# CM_FPGA_B0-1.net
KiCad netlist of a schematic drawn in Altium Designer
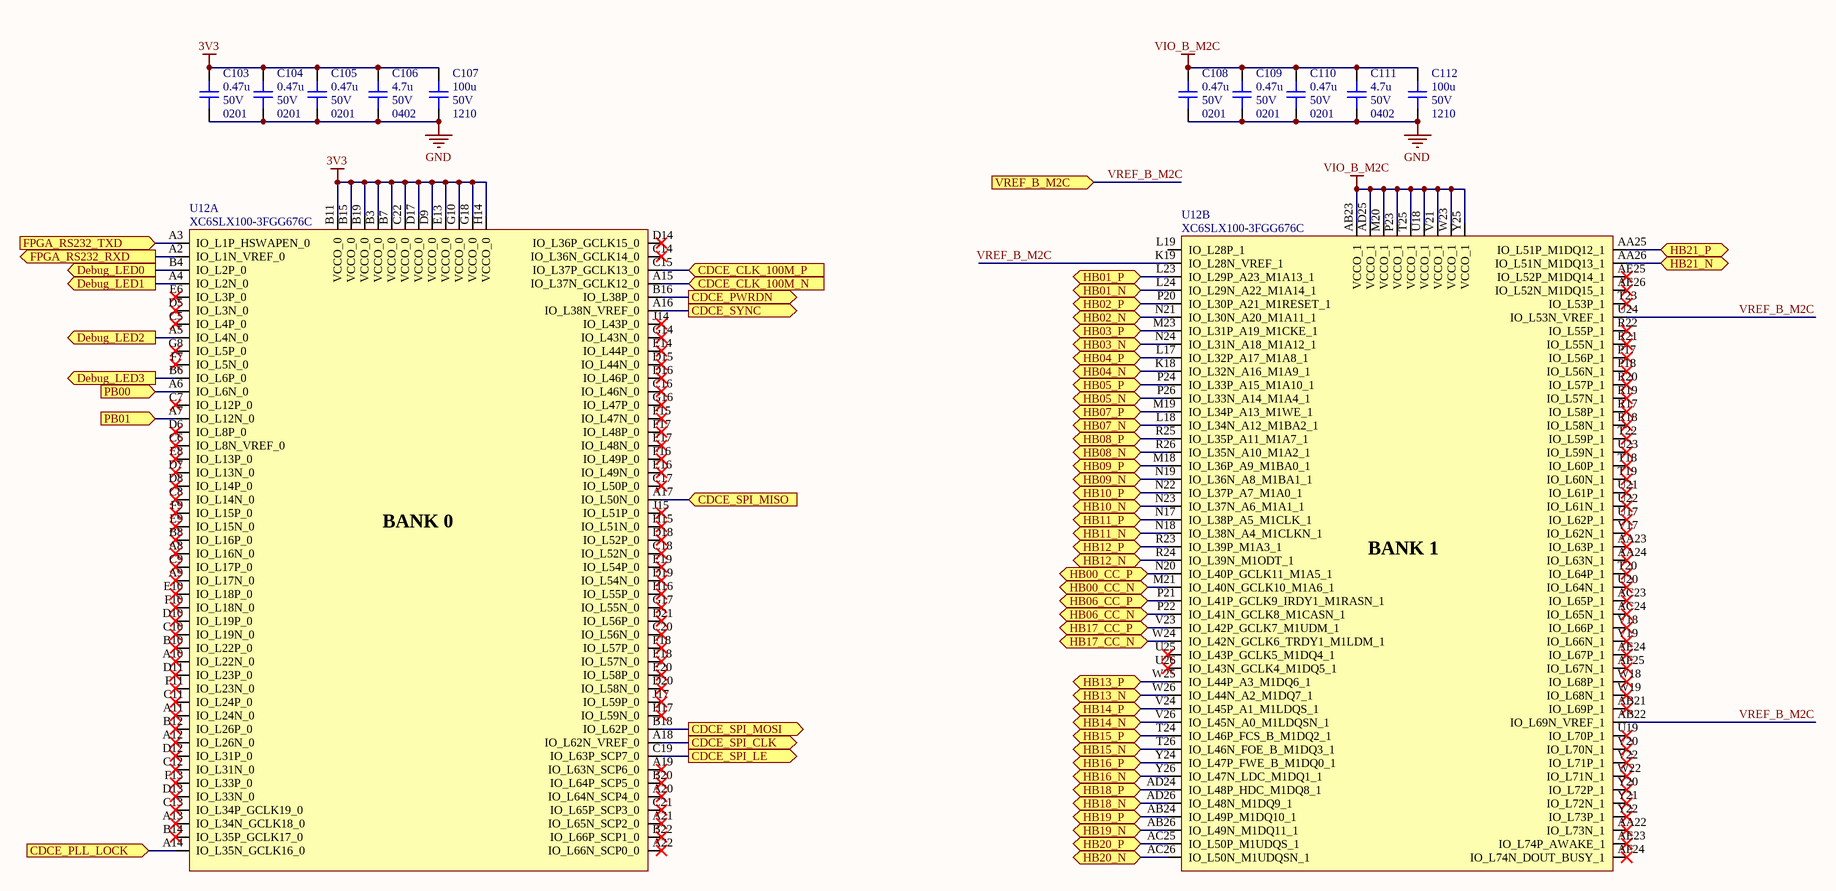
[diagram p0: CM_FPGA_B0-1.SchDoc]

(export (version "E")
  (design (tool "Eeschema 10.0.6"))
  (components
    (comp (ref "C103")
      (value "0.47u")
      (footprint "CAP_0201")
      (description "CAP - 0201")
      (fields
        (field (name "VOLTAGE") "50V")
        (field (name "PACKAGE") "0201")
        (field (name "CREATEDBY") "Jonathan Bouchard")
      )
      (libsource (lib "S7CAS_Lib2019_REV1_00") (part "CAP - 0201"))
    )
    (comp (ref "C104")
      (value "0.47u")
      (footprint "CAP_0201")
      (description "CAP - 0201")
      (fields
        (field (name "VOLTAGE") "50V")
        (field (name "PACKAGE") "0201")
        (field (name "CREATEDBY") "Jonathan Bouchard")
      )
      (libsource (lib "S7CAS_Lib2019_REV1_00") (part "CAP - 0201"))
    )
    (comp (ref "C105")
      (value "0.47u")
      (footprint "CAP_0201")
      (description "CAP - 0201")
      (fields
        (field (name "VOLTAGE") "50V")
        (field (name "PACKAGE") "0201")
        (field (name "CREATEDBY") "Jonathan Bouchard")
      )
      (libsource (lib "S7CAS_Lib2019_REV1_00") (part "CAP - 0201"))
    )
    (comp (ref "C106")
      (value "4.7u")
      (footprint "CAP_0402")
      (description "CAP - 0402")
      (fields
        (field (name "VOLTAGE") "50V")
        (field (name "PACKAGE") "0402")
        (field (name "CREATEDBY") "Jonathan Bouchard")
      )
      (libsource (lib "S7CAS_Lib2019_REV1_00") (part "CAP - 0402"))
    )
    (comp (ref "C107")
      (value "100u")
      (footprint "CAP_1210")
      (description "CAP - 1210")
      (fields
        (field (name "VOLTAGE") "50V")
        (field (name "PACKAGE") "1210")
        (field (name "CREATEDBY") "Jonathan Bouchard")
      )
      (libsource (lib "S7CAS_Lib2019_REV1_00") (part "CAP - 1210"))
    )
    (comp (ref "C108")
      (value "0.47u")
      (footprint "CAP_0201")
      (description "CAP - 0201")
      (fields
        (field (name "VOLTAGE") "50V")
        (field (name "PACKAGE") "0201")
        (field (name "CREATEDBY") "Jonathan Bouchard")
      )
      (libsource (lib "S7CAS_Lib2019_REV1_00") (part "CAP - 0201"))
    )
    (comp (ref "C109")
      (value "0.47u")
      (footprint "CAP_0201")
      (description "CAP - 0201")
      (fields
        (field (name "VOLTAGE") "50V")
        (field (name "PACKAGE") "0201")
        (field (name "CREATEDBY") "Jonathan Bouchard")
      )
      (libsource (lib "S7CAS_Lib2019_REV1_00") (part "CAP - 0201"))
    )
    (comp (ref "C110")
      (value "0.47u")
      (footprint "CAP_0201")
      (description "CAP - 0201")
      (fields
        (field (name "VOLTAGE") "50V")
        (field (name "PACKAGE") "0201")
        (field (name "CREATEDBY") "Jonathan Bouchard")
      )
      (libsource (lib "S7CAS_Lib2019_REV1_00") (part "CAP - 0201"))
    )
    (comp (ref "C111")
      (value "4.7u")
      (footprint "CAP_0402")
      (description "CAP - 0402")
      (fields
        (field (name "VOLTAGE") "50V")
        (field (name "PACKAGE") "0402")
        (field (name "CREATEDBY") "Jonathan Bouchard")
      )
      (libsource (lib "S7CAS_Lib2019_REV1_00") (part "CAP - 0402"))
    )
    (comp (ref "C112")
      (value "100u")
      (footprint "CAP_1210")
      (description "CAP - 1210")
      (fields
        (field (name "VOLTAGE") "50V")
        (field (name "PACKAGE") "1210")
        (field (name "CREATEDBY") "Jonathan Bouchard")
      )
      (libsource (lib "S7CAS_Lib2019_REV1_00") (part "CAP - 1210"))
    )
    (comp (ref "U12")
      (value "XC6SLX100-3FGG676C")
      (footprint "FPGA_XILINX_FGG676")
      (description "FPGA - XILINX SPARTAN 6 480 I/O - BGA-676")
      (fields
        (field (name "VOLTAGE") "1.14 V ~ 1.26 V")
        (field (name "MFG") "Xilinx")
        (field (name "CREATEDBY") "Jonathan Bouchard")
      )
      (libsource (lib "S7CAS_Lib2019_REV1_00") (part "FPGA_XC6SLX100-3FGG676C"))
    )
  )
  (nets
    (net (code "1") (name "/CDCE_CLK_100M_N") (class "Default")
      (node (ref "U12") (pin "A15") (pinfunction "IO_L37N_GCLK12_0_A15") (pintype "passive"))
    )
    (net (code "2") (name "/CDCE_CLK_100M_P") (class "Default")
      (node (ref "U12") (pin "C15") (pinfunction "IO_L37P_GCLK13_0_C15") (pintype "passive"))
    )
    (net (code "3") (name "/CDCE_PLL_LOCK") (class "Default")
      (node (ref "U12") (pin "A14") (pinfunction "IO_L35N_GCLK16_0_A14") (pintype "passive"))
    )
    (net (code "4") (name "/CDCE_PWRDN") (class "Default")
      (node (ref "U12") (pin "B16") (pinfunction "IO_L38P_0_B16") (pintype "passive"))
    )
    (net (code "5") (name "/CDCE_SPI_CLK") (class "Default")
      (node (ref "U12") (pin "A18") (pinfunction "IO_L62N_VREF_0_A18") (pintype "passive"))
    )
    (net (code "6") (name "/CDCE_SPI_LE") (class "Default")
      (node (ref "U12") (pin "C19") (pinfunction "IO_L63P_SCP7_0_C19") (pintype "passive"))
    )
    (net (code "7") (name "/CDCE_SPI_MISO") (class "Default")
      (node (ref "U12") (pin "A17") (pinfunction "IO_L50N_0_A17") (pintype "passive"))
    )
    (net (code "8") (name "/CDCE_SPI_MOSI") (class "Default")
      (node (ref "U12") (pin "B18") (pinfunction "IO_L62P_0_B18") (pintype "passive"))
    )
    (net (code "9") (name "/CDCE_SYNC") (class "Default")
      (node (ref "U12") (pin "A16") (pinfunction "IO_L38N_VREF_0_A16") (pintype "passive"))
    )
    (net (code "10") (name "/Debug_LED0") (class "Default")
      (node (ref "U12") (pin "B4") (pinfunction "IO_L2P_0_B4") (pintype "passive"))
    )
    (net (code "11") (name "/Debug_LED1") (class "Default")
      (node (ref "U12") (pin "A4") (pinfunction "IO_L2N_0_A4") (pintype "passive"))
    )
    (net (code "12") (name "/Debug_LED2") (class "Default")
      (node (ref "U12") (pin "A5") (pinfunction "IO_L4N_0_A5") (pintype "passive"))
    )
    (net (code "13") (name "/Debug_LED3") (class "Default")
      (node (ref "U12") (pin "B6") (pinfunction "IO_L6P_0_B6") (pintype "passive"))
    )
    (net (code "14") (name "/FPGA_RS232_RXD") (class "Default")
      (node (ref "U12") (pin "A2") (pinfunction "IO_L1N_VREF_0_A2") (pintype "passive"))
    )
    (net (code "15") (name "/FPGA_RS232_TXD") (class "Default")
      (node (ref "U12") (pin "A3") (pinfunction "IO_L1P_HSWAPEN_0_A3") (pintype "passive"))
    )
    (net (code "16") (name "/HB00_CC_N") (class "Default")
      (node (ref "U12") (pin "M21") (pinfunction "IO_L40N_GCLK10_M1A6_1_M21") (pintype "passive"))
    )
    (net (code "17") (name "/HB00_CC_P") (class "Default")
      (node (ref "U12") (pin "N20") (pinfunction "IO_L40P_GCLK11_M1A5_1_N20") (pintype "passive"))
    )
    (net (code "18") (name "/HB01_N") (class "Default")
      (node (ref "U12") (pin "L24") (pinfunction "IO_L29N_A22_M1A14_1_L24") (pintype "passive"))
    )
    (net (code "19") (name "/HB01_P") (class "Default")
      (node (ref "U12") (pin "L23") (pinfunction "IO_L29P_A23_M1A13_1_L23") (pintype "passive"))
    )
    (net (code "20") (name "/HB02_N") (class "Default")
      (node (ref "U12") (pin "N21") (pinfunction "IO_L30N_A20_M1A11_1_N21") (pintype "passive"))
    )
    (net (code "21") (name "/HB02_P") (class "Default")
      (node (ref "U12") (pin "P20") (pinfunction "IO_L30P_A21_M1RESET_1_P20") (pintype "passive"))
    )
    (net (code "22") (name "/HB03_N") (class "Default")
      (node (ref "U12") (pin "N24") (pinfunction "IO_L31N_A18_M1A12_1_N24") (pintype "passive"))
    )
    (net (code "23") (name "/HB03_P") (class "Default")
      (node (ref "U12") (pin "M23") (pinfunction "IO_L31P_A19_M1CKE_1_M23") (pintype "passive"))
    )
    (net (code "24") (name "/HB04_N") (class "Default")
      (node (ref "U12") (pin "K18") (pinfunction "IO_L32N_A16_M1A9_1_K18") (pintype "passive"))
    )
    (net (code "25") (name "/HB04_P") (class "Default")
      (node (ref "U12") (pin "L17") (pinfunction "IO_L32P_A17_M1A8_1_L17") (pintype "passive"))
    )
    (net (code "26") (name "/HB05_N") (class "Default")
      (node (ref "U12") (pin "P26") (pinfunction "IO_L33N_A14_M1A4_1_P26") (pintype "passive"))
    )
    (net (code "27") (name "/HB05_P") (class "Default")
      (node (ref "U12") (pin "P24") (pinfunction "IO_L33P_A15_M1A10_1_P24") (pintype "passive"))
    )
    (net (code "28") (name "/HB06_CC_N") (class "Default")
      (node (ref "U12") (pin "P22") (pinfunction "IO_L41N_GCLK8_M1CASN_1_P22") (pintype "passive"))
    )
    (net (code "29") (name "/HB06_CC_P") (class "Default")
      (node (ref "U12") (pin "P21") (pinfunction "IO_L41P_GCLK9_IRDY1_M1RASN_1_P21") (pintype "passive"))
    )
    (net (code "30") (name "/HB07_N") (class "Default")
      (node (ref "U12") (pin "L18") (pinfunction "IO_L34N_A12_M1BA2_1_L18") (pintype "passive"))
    )
    (net (code "31") (name "/HB07_P") (class "Default")
      (node (ref "U12") (pin "M19") (pinfunction "IO_L34P_A13_M1WE_1_M19") (pintype "passive"))
    )
    (net (code "32") (name "/HB08_N") (class "Default")
      (node (ref "U12") (pin "R26") (pinfunction "IO_L35N_A10_M1A2_1_R26") (pintype "passive"))
    )
    (net (code "33") (name "/HB08_P") (class "Default")
      (node (ref "U12") (pin "R25") (pinfunction "IO_L35P_A11_M1A7_1_R25") (pintype "passive"))
    )
    (net (code "34") (name "/HB09_N") (class "Default")
      (node (ref "U12") (pin "N19") (pinfunction "IO_L36N_A8_M1BA1_1_N19") (pintype "passive"))
    )
    (net (code "35") (name "/HB09_P") (class "Default")
      (node (ref "U12") (pin "M18") (pinfunction "IO_L36P_A9_M1BA0_1_M18") (pintype "passive"))
    )
    (net (code "36") (name "/HB10_N") (class "Default")
      (node (ref "U12") (pin "N23") (pinfunction "IO_L37N_A6_M1A1_1_N23") (pintype "passive"))
    )
    (net (code "37") (name "/HB10_P") (class "Default")
      (node (ref "U12") (pin "N22") (pinfunction "IO_L37P_A7_M1A0_1_N22") (pintype "passive"))
    )
    (net (code "38") (name "/HB11_N") (class "Default")
      (node (ref "U12") (pin "N18") (pinfunction "IO_L38N_A4_M1CLKN_1_N18") (pintype "passive"))
    )
    (net (code "39") (name "/HB11_P") (class "Default")
      (node (ref "U12") (pin "N17") (pinfunction "IO_L38P_A5_M1CLK_1_N17") (pintype "passive"))
    )
    (net (code "40") (name "/HB12_N") (class "Default")
      (node (ref "U12") (pin "R24") (pinfunction "IO_L39N_M1ODT_1_R24") (pintype "passive"))
    )
    (net (code "41") (name "/HB12_P") (class "Default")
      (node (ref "U12") (pin "R23") (pinfunction "IO_L39P_M1A3_1_R23") (pintype "passive"))
    )
    (net (code "42") (name "/HB13_N") (class "Default")
      (node (ref "U12") (pin "W26") (pinfunction "IO_L44N_A2_M1DQ7_1_W26") (pintype "passive"))
    )
    (net (code "43") (name "/HB13_P") (class "Default")
      (node (ref "U12") (pin "W25") (pinfunction "IO_L44P_A3_M1DQ6_1_W25") (pintype "passive"))
    )
    (net (code "44") (name "/HB14_N") (class "Default")
      (node (ref "U12") (pin "V26") (pinfunction "IO_L45N_A0_M1LDQSN_1_V26") (pintype "passive"))
    )
    (net (code "45") (name "/HB14_P") (class "Default")
      (node (ref "U12") (pin "V24") (pinfunction "IO_L45P_A1_M1LDQS_1_V24") (pintype "passive"))
    )
    (net (code "46") (name "/HB15_N") (class "Default")
      (node (ref "U12") (pin "T26") (pinfunction "IO_L46N_FOE_B_M1DQ3_1_T26") (pintype "passive"))
    )
    (net (code "47") (name "/HB15_P") (class "Default")
      (node (ref "U12") (pin "T24") (pinfunction "IO_L46P_FCS_B_M1DQ2_1_T24") (pintype "passive"))
    )
    (net (code "48") (name "/HB16_N") (class "Default")
      (node (ref "U12") (pin "Y26") (pinfunction "IO_L47N_LDC_M1DQ1_1_Y26") (pintype "passive"))
    )
    (net (code "49") (name "/HB16_P") (class "Default")
      (node (ref "U12") (pin "Y24") (pinfunction "IO_L47P_FWE_B_M1DQ0_1_Y24") (pintype "passive"))
    )
    (net (code "50") (name "/HB17_CC_N") (class "Default")
      (node (ref "U12") (pin "W24") (pinfunction "IO_L42N_GCLK6_TRDY1_M1LDM_1_W24") (pintype "passive"))
    )
    (net (code "51") (name "/HB17_CC_P") (class "Default")
      (node (ref "U12") (pin "V23") (pinfunction "IO_L42P_GCLK7_M1UDM_1_V23") (pintype "passive"))
    )
    (net (code "52") (name "/HB18_N") (class "Default")
      (node (ref "U12") (pin "AD26") (pinfunction "IO_L48N_M1DQ9_1_AD26") (pintype "passive"))
    )
    (net (code "53") (name "/HB18_P") (class "Default")
      (node (ref "U12") (pin "AD24") (pinfunction "IO_L48P_HDC_M1DQ8_1_AD24") (pintype "passive"))
    )
    (net (code "54") (name "/HB19_N") (class "Default")
      (node (ref "U12") (pin "AB26") (pinfunction "IO_L49N_M1DQ11_1_AB26") (pintype "passive"))
    )
    (net (code "55") (name "/HB19_P") (class "Default")
      (node (ref "U12") (pin "AB24") (pinfunction "IO_L49P_M1DQ10_1_AB24") (pintype "passive"))
    )
    (net (code "56") (name "/HB20_N") (class "Default")
      (node (ref "U12") (pin "AC26") (pinfunction "IO_L50N_M1UDQSN_1_AC26") (pintype "passive"))
    )
    (net (code "57") (name "/HB20_P") (class "Default")
      (node (ref "U12") (pin "AC25") (pinfunction "IO_L50P_M1UDQS_1_AC25") (pintype "passive"))
    )
    (net (code "58") (name "/HB21_N") (class "Default")
      (node (ref "U12") (pin "AA26") (pinfunction "IO_L51N_M1DQ13_1_AA26") (pintype "passive"))
    )
    (net (code "59") (name "/HB21_P") (class "Default")
      (node (ref "U12") (pin "AA25") (pinfunction "IO_L51P_M1DQ12_1_AA25") (pintype "passive"))
    )
    (net (code "60") (name "/PB00") (class "Default")
      (node (ref "U12") (pin "A6") (pinfunction "IO_L6N_0_A6") (pintype "passive"))
    )
    (net (code "61") (name "/PB01") (class "Default")
      (node (ref "U12") (pin "A7") (pinfunction "IO_L12N_0_A7") (pintype "passive"))
    )
    (net (code "62") (name "/VREF_B_M2C") (class "Default")
      (node (ref "U12") (pin "AB22") (pinfunction "IO_L69N_VREF_1_AB22") (pintype "passive"))
      (node (ref "U12") (pin "K19") (pinfunction "IO_L28N_VREF_1_K19") (pintype "passive"))
      (node (ref "U12") (pin "U24") (pinfunction "IO_L53N_VREF_1_U24") (pintype "passive"))
    )
    (net (code "63") (name "3V3") (class "Default")
      (node (ref "C103") (pin "2") (pinfunction "2_2") (pintype "passive"))
      (node (ref "C104") (pin "2") (pinfunction "2_2") (pintype "passive"))
      (node (ref "C105") (pin "2") (pinfunction "2_2") (pintype "passive"))
      (node (ref "C106") (pin "2") (pinfunction "2_2") (pintype "passive"))
      (node (ref "C107") (pin "2") (pinfunction "2_2") (pintype "passive"))
      (node (ref "U12") (pin "B11") (pinfunction "VCCO_0_B11") (pintype "passive"))
      (node (ref "U12") (pin "B15") (pinfunction "VCCO_0_B15") (pintype "passive"))
      (node (ref "U12") (pin "B19") (pinfunction "VCCO_0_B19") (pintype "passive"))
      (node (ref "U12") (pin "B3") (pinfunction "VCCO_0_B3") (pintype "passive"))
      (node (ref "U12") (pin "B7") (pinfunction "VCCO_0_B7") (pintype "passive"))
      (node (ref "U12") (pin "C22") (pinfunction "VCCO_0_C22") (pintype "passive"))
      (node (ref "U12") (pin "D17") (pinfunction "VCCO_0_D17") (pintype "passive"))
      (node (ref "U12") (pin "D9") (pinfunction "VCCO_0_D9") (pintype "passive"))
      (node (ref "U12") (pin "E13") (pinfunction "VCCO_0_E13") (pintype "passive"))
      (node (ref "U12") (pin "G10") (pinfunction "VCCO_0_G10") (pintype "passive"))
      (node (ref "U12") (pin "G18") (pinfunction "VCCO_0_G18") (pintype "passive"))
      (node (ref "U12") (pin "H14") (pinfunction "VCCO_0_H14") (pintype "passive"))
    )
    (net (code "64") (name "GND") (class "Default")
      (node (ref "C103") (pin "1") (pinfunction "1_1") (pintype "passive"))
      (node (ref "C104") (pin "1") (pinfunction "1_1") (pintype "passive"))
      (node (ref "C105") (pin "1") (pinfunction "1_1") (pintype "passive"))
      (node (ref "C106") (pin "1") (pinfunction "1_1") (pintype "passive"))
      (node (ref "C107") (pin "1") (pinfunction "1_1") (pintype "passive"))
      (node (ref "C108") (pin "1") (pinfunction "1_1") (pintype "passive"))
      (node (ref "C109") (pin "1") (pinfunction "1_1") (pintype "passive"))
      (node (ref "C110") (pin "1") (pinfunction "1_1") (pintype "passive"))
      (node (ref "C111") (pin "1") (pinfunction "1_1") (pintype "passive"))
      (node (ref "C112") (pin "1") (pinfunction "1_1") (pintype "passive"))
    )
    (net (code "65") (name "VIO_B_M2C") (class "Default")
      (node (ref "C108") (pin "2") (pinfunction "2_2") (pintype "passive"))
      (node (ref "C109") (pin "2") (pinfunction "2_2") (pintype "passive"))
      (node (ref "C110") (pin "2") (pinfunction "2_2") (pintype "passive"))
      (node (ref "C111") (pin "2") (pinfunction "2_2") (pintype "passive"))
      (node (ref "C112") (pin "2") (pinfunction "2_2") (pintype "passive"))
      (node (ref "U12") (pin "AB23") (pinfunction "VCCO_1_AB23") (pintype "passive"))
      (node (ref "U12") (pin "AD25") (pinfunction "VCCO_1_AD25") (pintype "passive"))
      (node (ref "U12") (pin "M20") (pinfunction "VCCO_1_M20") (pintype "passive"))
      (node (ref "U12") (pin "P23") (pinfunction "VCCO_1_P23") (pintype "passive"))
      (node (ref "U12") (pin "T25") (pinfunction "VCCO_1_T25") (pintype "passive"))
      (node (ref "U12") (pin "U18") (pinfunction "VCCO_1_U18") (pintype "passive"))
      (node (ref "U12") (pin "V21") (pinfunction "VCCO_1_V21") (pintype "passive"))
      (node (ref "U12") (pin "W23") (pinfunction "VCCO_1_W23") (pintype "passive"))
      (node (ref "U12") (pin "Y25") (pinfunction "VCCO_1_Y25") (pintype "passive"))
    )
    (net (code "66") (name "unconnected-(U12A-IO_L3N_0-PadD5)") (class "Default")
      (node (ref "U12") (pin "D5") (pinfunction "IO_L3N_0_D5") (pintype "passive+no_connect"))
    )
    (net (code "67") (name "unconnected-(U12A-IO_L3P_0-PadE6)") (class "Default")
      (node (ref "U12") (pin "E6") (pinfunction "IO_L3P_0_E6") (pintype "passive+no_connect"))
    )
    (net (code "68") (name "unconnected-(U12A-IO_L4P_0-PadC5)") (class "Default")
      (node (ref "U12") (pin "C5") (pinfunction "IO_L4P_0_C5") (pintype "passive+no_connect"))
    )
    (net (code "69") (name "unconnected-(U12A-IO_L5N_0-PadF7)") (class "Default")
      (node (ref "U12") (pin "F7") (pinfunction "IO_L5N_0_F7") (pintype "passive+no_connect"))
    )
    (net (code "70") (name "unconnected-(U12A-IO_L5P_0-PadG8)") (class "Default")
      (node (ref "U12") (pin "G8") (pinfunction "IO_L5P_0_G8") (pintype "passive+no_connect"))
    )
    (net (code "71") (name "unconnected-(U12A-IO_L8N_VREF_0-PadC6)") (class "Default")
      (node (ref "U12") (pin "C6") (pinfunction "IO_L8N_VREF_0_C6") (pintype "passive+no_connect"))
    )
    (net (code "72") (name "unconnected-(U12A-IO_L8P_0-PadD6)") (class "Default")
      (node (ref "U12") (pin "D6") (pinfunction "IO_L8P_0_D6") (pintype "passive+no_connect"))
    )
    (net (code "73") (name "unconnected-(U12A-IO_L12P_0-PadC7)") (class "Default")
      (node (ref "U12") (pin "C7") (pinfunction "IO_L12P_0_C7") (pintype "passive+no_connect"))
    )
    (net (code "74") (name "unconnected-(U12A-IO_L13N_0-PadD7)") (class "Default")
      (node (ref "U12") (pin "D7") (pinfunction "IO_L13N_0_D7") (pintype "passive+no_connect"))
    )
    (net (code "75") (name "unconnected-(U12A-IO_L13P_0-PadE8)") (class "Default")
      (node (ref "U12") (pin "E8") (pinfunction "IO_L13P_0_E8") (pintype "passive+no_connect"))
    )
    (net (code "76") (name "unconnected-(U12A-IO_L14N_0-PadC8)") (class "Default")
      (node (ref "U12") (pin "C8") (pinfunction "IO_L14N_0_C8") (pintype "passive+no_connect"))
    )
    (net (code "77") (name "unconnected-(U12A-IO_L14P_0-PadD8)") (class "Default")
      (node (ref "U12") (pin "D8") (pinfunction "IO_L14P_0_D8") (pintype "passive+no_connect"))
    )
    (net (code "78") (name "unconnected-(U12A-IO_L15N_0-PadE9)") (class "Default")
      (node (ref "U12") (pin "E9") (pinfunction "IO_L15N_0_E9") (pintype "passive+no_connect"))
    )
    (net (code "79") (name "unconnected-(U12A-IO_L15P_0-PadF9)") (class "Default")
      (node (ref "U12") (pin "F9") (pinfunction "IO_L15P_0_F9") (pintype "passive+no_connect"))
    )
    (net (code "80") (name "unconnected-(U12A-IO_L16N_0-PadA8)") (class "Default")
      (node (ref "U12") (pin "A8") (pinfunction "IO_L16N_0_A8") (pintype "passive+no_connect"))
    )
    (net (code "81") (name "unconnected-(U12A-IO_L16P_0-PadB8)") (class "Default")
      (node (ref "U12") (pin "B8") (pinfunction "IO_L16P_0_B8") (pintype "passive+no_connect"))
    )
    (net (code "82") (name "unconnected-(U12A-IO_L17N_0-PadA9)") (class "Default")
      (node (ref "U12") (pin "A9") (pinfunction "IO_L17N_0_A9") (pintype "passive+no_connect"))
    )
    (net (code "83") (name "unconnected-(U12A-IO_L17P_0-PadC9)") (class "Default")
      (node (ref "U12") (pin "C9") (pinfunction "IO_L17P_0_C9") (pintype "passive+no_connect"))
    )
    (net (code "84") (name "unconnected-(U12A-IO_L18N_0-PadF10)") (class "Default")
      (node (ref "U12") (pin "F10") (pinfunction "IO_L18N_0_F10") (pintype "passive+no_connect"))
    )
    (net (code "85") (name "unconnected-(U12A-IO_L18P_0-PadE10)") (class "Default")
      (node (ref "U12") (pin "E10") (pinfunction "IO_L18P_0_E10") (pintype "passive+no_connect"))
    )
    (net (code "86") (name "unconnected-(U12A-IO_L19N_0-PadC10)") (class "Default")
      (node (ref "U12") (pin "C10") (pinfunction "IO_L19N_0_C10") (pintype "passive+no_connect"))
    )
    (net (code "87") (name "unconnected-(U12A-IO_L19P_0-PadD10)") (class "Default")
      (node (ref "U12") (pin "D10") (pinfunction "IO_L19P_0_D10") (pintype "passive+no_connect"))
    )
    (net (code "88") (name "unconnected-(U12A-IO_L22N_0-PadA10)") (class "Default")
      (node (ref "U12") (pin "A10") (pinfunction "IO_L22N_0_A10") (pintype "passive+no_connect"))
    )
    (net (code "89") (name "unconnected-(U12A-IO_L22P_0-PadB10)") (class "Default")
      (node (ref "U12") (pin "B10") (pinfunction "IO_L22P_0_B10") (pintype "passive+no_connect"))
    )
    (net (code "90") (name "unconnected-(U12A-IO_L23N_0-PadF11)") (class "Default")
      (node (ref "U12") (pin "F11") (pinfunction "IO_L23N_0_F11") (pintype "passive+no_connect"))
    )
    (net (code "91") (name "unconnected-(U12A-IO_L23P_0-PadD11)") (class "Default")
      (node (ref "U12") (pin "D11") (pinfunction "IO_L23P_0_D11") (pintype "passive+no_connect"))
    )
    (net (code "92") (name "unconnected-(U12A-IO_L24N_0-PadA11)") (class "Default")
      (node (ref "U12") (pin "A11") (pinfunction "IO_L24N_0_A11") (pintype "passive+no_connect"))
    )
    (net (code "93") (name "unconnected-(U12A-IO_L24P_0-PadC11)") (class "Default")
      (node (ref "U12") (pin "C11") (pinfunction "IO_L24P_0_C11") (pintype "passive+no_connect"))
    )
    (net (code "94") (name "unconnected-(U12A-IO_L26N_0-PadA12)") (class "Default")
      (node (ref "U12") (pin "A12") (pinfunction "IO_L26N_0_A12") (pintype "passive+no_connect"))
    )
    (net (code "95") (name "unconnected-(U12A-IO_L26P_0-PadB12)") (class "Default")
      (node (ref "U12") (pin "B12") (pinfunction "IO_L26P_0_B12") (pintype "passive+no_connect"))
    )
    (net (code "96") (name "unconnected-(U12A-IO_L31N_0-PadC12)") (class "Default")
      (node (ref "U12") (pin "C12") (pinfunction "IO_L31N_0_C12") (pintype "passive+no_connect"))
    )
    (net (code "97") (name "unconnected-(U12A-IO_L31P_0-PadD12)") (class "Default")
      (node (ref "U12") (pin "D12") (pinfunction "IO_L31P_0_D12") (pintype "passive+no_connect"))
    )
    (net (code "98") (name "unconnected-(U12A-IO_L33N_0-PadD13)") (class "Default")
      (node (ref "U12") (pin "D13") (pinfunction "IO_L33N_0_D13") (pintype "passive+no_connect"))
    )
    (net (code "99") (name "unconnected-(U12A-IO_L33P_0-PadF13)") (class "Default")
      (node (ref "U12") (pin "F13") (pinfunction "IO_L33P_0_F13") (pintype "passive+no_connect"))
    )
    (net (code "100") (name "unconnected-(U12A-IO_L34N_GCLK18_0-PadA13)") (class "Default")
      (node (ref "U12") (pin "A13") (pinfunction "IO_L34N_GCLK18_0_A13") (pintype "passive+no_connect"))
    )
    (net (code "101") (name "unconnected-(U12A-IO_L34P_GCLK19_0-PadC13)") (class "Default")
      (node (ref "U12") (pin "C13") (pinfunction "IO_L34P_GCLK19_0_C13") (pintype "passive+no_connect"))
    )
    (net (code "102") (name "unconnected-(U12A-IO_L35P_GCLK17_0-PadB14)") (class "Default")
      (node (ref "U12") (pin "B14") (pinfunction "IO_L35P_GCLK17_0_B14") (pintype "passive+no_connect"))
    )
    (net (code "103") (name "unconnected-(U12A-IO_L36N_GCLK14_0-PadC14)") (class "Default")
      (node (ref "U12") (pin "C14") (pinfunction "IO_L36N_GCLK14_0_C14") (pintype "passive+no_connect"))
    )
    (net (code "104") (name "unconnected-(U12A-IO_L36P_GCLK15_0-PadD14)") (class "Default")
      (node (ref "U12") (pin "D14") (pinfunction "IO_L36P_GCLK15_0_D14") (pintype "passive+no_connect"))
    )
    (net (code "105") (name "unconnected-(U12A-IO_L43N_0-PadG14)") (class "Default")
      (node (ref "U12") (pin "G14") (pinfunction "IO_L43N_0_G14") (pintype "passive+no_connect"))
    )
    (net (code "106") (name "unconnected-(U12A-IO_L43P_0-PadJ14)") (class "Default")
      (node (ref "U12") (pin "J14") (pinfunction "IO_L43P_0_J14") (pintype "passive+no_connect"))
    )
    (net (code "107") (name "unconnected-(U12A-IO_L44N_0-PadD15)") (class "Default")
      (node (ref "U12") (pin "D15") (pinfunction "IO_L44N_0_D15") (pintype "passive+no_connect"))
    )
    (net (code "108") (name "unconnected-(U12A-IO_L44P_0-PadE14)") (class "Default")
      (node (ref "U12") (pin "E14") (pinfunction "IO_L44P_0_E14") (pintype "passive+no_connect"))
    )
    (net (code "109") (name "unconnected-(U12A-IO_L46N_0-PadC16)") (class "Default")
      (node (ref "U12") (pin "C16") (pinfunction "IO_L46N_0_C16") (pintype "passive+no_connect"))
    )
    (net (code "110") (name "unconnected-(U12A-IO_L46P_0-PadD16)") (class "Default")
      (node (ref "U12") (pin "D16") (pinfunction "IO_L46P_0_D16") (pintype "passive+no_connect"))
    )
    (net (code "111") (name "unconnected-(U12A-IO_L47N_0-PadF15)") (class "Default")
      (node (ref "U12") (pin "F15") (pinfunction "IO_L47N_0_F15") (pintype "passive+no_connect"))
    )
    (net (code "112") (name "unconnected-(U12A-IO_L47P_0-PadG16)") (class "Default")
      (node (ref "U12") (pin "G16") (pinfunction "IO_L47P_0_G16") (pintype "passive+no_connect"))
    )
    (net (code "113") (name "unconnected-(U12A-IO_L48N_0-PadE17)") (class "Default")
      (node (ref "U12") (pin "E17") (pinfunction "IO_L48N_0_E17") (pintype "passive+no_connect"))
    )
    (net (code "114") (name "unconnected-(U12A-IO_L48P_0-PadF17)") (class "Default")
      (node (ref "U12") (pin "F17") (pinfunction "IO_L48P_0_F17") (pintype "passive+no_connect"))
    )
    (net (code "115") (name "unconnected-(U12A-IO_L49N_0-PadE16)") (class "Default")
      (node (ref "U12") (pin "E16") (pinfunction "IO_L49N_0_E16") (pintype "passive+no_connect"))
    )
    (net (code "116") (name "unconnected-(U12A-IO_L49P_0-PadF16)") (class "Default")
      (node (ref "U12") (pin "F16") (pinfunction "IO_L49P_0_F16") (pintype "passive+no_connect"))
    )
    (net (code "117") (name "unconnected-(U12A-IO_L50P_0-PadC17)") (class "Default")
      (node (ref "U12") (pin "C17") (pinfunction "IO_L50P_0_C17") (pintype "passive+no_connect"))
    )
    (net (code "118") (name "unconnected-(U12A-IO_L51N_0-PadH15)") (class "Default")
      (node (ref "U12") (pin "H15") (pinfunction "IO_L51N_0_H15") (pintype "passive+no_connect"))
    )
    (net (code "119") (name "unconnected-(U12A-IO_L51P_0-PadJ15)") (class "Default")
      (node (ref "U12") (pin "J15") (pinfunction "IO_L51P_0_J15") (pintype "passive+no_connect"))
    )
    (net (code "120") (name "unconnected-(U12A-IO_L52N_0-PadC18)") (class "Default")
      (node (ref "U12") (pin "C18") (pinfunction "IO_L52N_0_C18") (pintype "passive+no_connect"))
    )
    (net (code "121") (name "unconnected-(U12A-IO_L52P_0-PadD18)") (class "Default")
      (node (ref "U12") (pin "D18") (pinfunction "IO_L52P_0_D18") (pintype "passive+no_connect"))
    )
    (net (code "122") (name "unconnected-(U12A-IO_L54N_0-PadD19)") (class "Default")
      (node (ref "U12") (pin "D19") (pinfunction "IO_L54N_0_D19") (pintype "passive+no_connect"))
    )
    (net (code "123") (name "unconnected-(U12A-IO_L54P_0-PadE19)") (class "Default")
      (node (ref "U12") (pin "E19") (pinfunction "IO_L54P_0_E19") (pintype "passive+no_connect"))
    )
    (net (code "124") (name "unconnected-(U12A-IO_L55N_0-PadG17)") (class "Default")
      (node (ref "U12") (pin "G17") (pinfunction "IO_L55N_0_G17") (pintype "passive+no_connect"))
    )
    (net (code "125") (name "unconnected-(U12A-IO_L55P_0-PadH16)") (class "Default")
      (node (ref "U12") (pin "H16") (pinfunction "IO_L55P_0_H16") (pintype "passive+no_connect"))
    )
    (net (code "126") (name "unconnected-(U12A-IO_L56N_0-PadC20)") (class "Default")
      (node (ref "U12") (pin "C20") (pinfunction "IO_L56N_0_C20") (pintype "passive+no_connect"))
    )
    (net (code "127") (name "unconnected-(U12A-IO_L56P_0-PadD21)") (class "Default")
      (node (ref "U12") (pin "D21") (pinfunction "IO_L56P_0_D21") (pintype "passive+no_connect"))
    )
    (net (code "128") (name "unconnected-(U12A-IO_L57N_0-PadE18)") (class "Default")
      (node (ref "U12") (pin "E18") (pinfunction "IO_L57N_0_E18") (pintype "passive+no_connect"))
    )
    (net (code "129") (name "unconnected-(U12A-IO_L57P_0-PadF18)") (class "Default")
      (node (ref "U12") (pin "F18") (pinfunction "IO_L57P_0_F18") (pintype "passive+no_connect"))
    )
    (net (code "130") (name "unconnected-(U12A-IO_L58N_0-PadD20)") (class "Default")
      (node (ref "U12") (pin "D20") (pinfunction "IO_L58N_0_D20") (pintype "passive+no_connect"))
    )
    (net (code "131") (name "unconnected-(U12A-IO_L58P_0-PadE20)") (class "Default")
      (node (ref "U12") (pin "E20") (pinfunction "IO_L58P_0_E20") (pintype "passive+no_connect"))
    )
    (net (code "132") (name "unconnected-(U12A-IO_L59N_0-PadH17)") (class "Default")
      (node (ref "U12") (pin "H17") (pinfunction "IO_L59N_0_H17") (pintype "passive+no_connect"))
    )
    (net (code "133") (name "unconnected-(U12A-IO_L59P_0-PadJ17)") (class "Default")
      (node (ref "U12") (pin "J17") (pinfunction "IO_L59P_0_J17") (pintype "passive+no_connect"))
    )
    (net (code "134") (name "unconnected-(U12A-IO_L63N_SCP6_0-PadA19)") (class "Default")
      (node (ref "U12") (pin "A19") (pinfunction "IO_L63N_SCP6_0_A19") (pintype "passive+no_connect"))
    )
    (net (code "135") (name "unconnected-(U12A-IO_L64N_SCP4_0-PadA20)") (class "Default")
      (node (ref "U12") (pin "A20") (pinfunction "IO_L64N_SCP4_0_A20") (pintype "passive+no_connect"))
    )
    (net (code "136") (name "unconnected-(U12A-IO_L64P_SCP5_0-PadB20)") (class "Default")
      (node (ref "U12") (pin "B20") (pinfunction "IO_L64P_SCP5_0_B20") (pintype "passive+no_connect"))
    )
    (net (code "137") (name "unconnected-(U12A-IO_L65N_SCP2_0-PadA21)") (class "Default")
      (node (ref "U12") (pin "A21") (pinfunction "IO_L65N_SCP2_0_A21") (pintype "passive+no_connect"))
    )
    (net (code "138") (name "unconnected-(U12A-IO_L65P_SCP3_0-PadC21)") (class "Default")
      (node (ref "U12") (pin "C21") (pinfunction "IO_L65P_SCP3_0_C21") (pintype "passive+no_connect"))
    )
    (net (code "139") (name "unconnected-(U12A-IO_L66N_SCP0_0-PadA22)") (class "Default")
      (node (ref "U12") (pin "A22") (pinfunction "IO_L66N_SCP0_0_A22") (pintype "passive+no_connect"))
    )
    (net (code "140") (name "unconnected-(U12A-IO_L66P_SCP1_0-PadB22)") (class "Default")
      (node (ref "U12") (pin "B22") (pinfunction "IO_L66P_SCP1_0_B22") (pintype "passive+no_connect"))
    )
    (net (code "141") (name "unconnected-(U12B-IO_L28P_1-PadL19)") (class "Default")
      (node (ref "U12") (pin "L19") (pinfunction "IO_L28P_1_L19") (pintype "passive"))
    )
    (net (code "142") (name "unconnected-(U12B-IO_L43N_GCLK4_M1DQ5_1-PadU26)") (class "Default")
      (node (ref "U12") (pin "U26") (pinfunction "IO_L43N_GCLK4_M1DQ5_1_U26") (pintype "passive+no_connect"))
    )
    (net (code "143") (name "unconnected-(U12B-IO_L43P_GCLK5_M1DQ4_1-PadU25)") (class "Default")
      (node (ref "U12") (pin "U25") (pinfunction "IO_L43P_GCLK5_M1DQ4_1_U25") (pintype "passive+no_connect"))
    )
    (net (code "144") (name "unconnected-(U12B-IO_L52N_M1DQ15_1-PadAE26)") (class "Default")
      (node (ref "U12") (pin "AE26") (pinfunction "IO_L52N_M1DQ15_1_AE26") (pintype "passive+no_connect"))
    )
    (net (code "145") (name "unconnected-(U12B-IO_L52P_M1DQ14_1-PadAE25)") (class "Default")
      (node (ref "U12") (pin "AE25") (pinfunction "IO_L52P_M1DQ14_1_AE25") (pintype "passive+no_connect"))
    )
    (net (code "146") (name "unconnected-(U12B-IO_L53P_1-PadT23)") (class "Default")
      (node (ref "U12") (pin "T23") (pinfunction "IO_L53P_1_T23") (pintype "passive+no_connect"))
    )
    (net (code "147") (name "unconnected-(U12B-IO_L55N_1-PadR21)") (class "Default")
      (node (ref "U12") (pin "R21") (pinfunction "IO_L55N_1_R21") (pintype "passive+no_connect"))
    )
    (net (code "148") (name "unconnected-(U12B-IO_L55P_1-PadR22)") (class "Default")
      (node (ref "U12") (pin "R22") (pinfunction "IO_L55P_1_R22") (pintype "passive+no_connect"))
    )
    (net (code "149") (name "unconnected-(U12B-IO_L56N_1-PadP18)") (class "Default")
      (node (ref "U12") (pin "P18") (pinfunction "IO_L56N_1_P18") (pintype "passive+no_connect"))
    )
    (net (code "150") (name "unconnected-(U12B-IO_L56P_1-PadP17)") (class "Default")
      (node (ref "U12") (pin "P17") (pinfunction "IO_L56P_1_P17") (pintype "passive+no_connect"))
    )
    (net (code "151") (name "unconnected-(U12B-IO_L57N_1-PadR19)") (class "Default")
      (node (ref "U12") (pin "R19") (pinfunction "IO_L57N_1_R19") (pintype "passive+no_connect"))
    )
    (net (code "152") (name "unconnected-(U12B-IO_L57P_1-PadR20)") (class "Default")
      (node (ref "U12") (pin "R20") (pinfunction "IO_L57P_1_R20") (pintype "passive+no_connect"))
    )
    (net (code "153") (name "unconnected-(U12B-IO_L58N_1-PadR18)") (class "Default")
      (node (ref "U12") (pin "R18") (pinfunction "IO_L58N_1_R18") (pintype "passive+no_connect"))
    )
    (net (code "154") (name "unconnected-(U12B-IO_L58P_1-PadR17)") (class "Default")
      (node (ref "U12") (pin "R17") (pinfunction "IO_L58P_1_R17") (pintype "passive+no_connect"))
    )
    (net (code "155") (name "unconnected-(U12B-IO_L59N_1-PadU23)") (class "Default")
      (node (ref "U12") (pin "U23") (pinfunction "IO_L59N_1_U23") (pintype "passive+no_connect"))
    )
    (net (code "156") (name "unconnected-(U12B-IO_L59P_1-PadT22)") (class "Default")
      (node (ref "U12") (pin "T22") (pinfunction "IO_L59P_1_T22") (pintype "passive+no_connect"))
    )
    (net (code "157") (name "unconnected-(U12B-IO_L60N_1-PadT19)") (class "Default")
      (node (ref "U12") (pin "T19") (pinfunction "IO_L60N_1_T19") (pintype "passive+no_connect"))
    )
    (net (code "158") (name "unconnected-(U12B-IO_L60P_1-PadT18)") (class "Default")
      (node (ref "U12") (pin "T18") (pinfunction "IO_L60P_1_T18") (pintype "passive+no_connect"))
    )
    (net (code "159") (name "unconnected-(U12B-IO_L61N_1-PadU22)") (class "Default")
      (node (ref "U12") (pin "U22") (pinfunction "IO_L61N_1_U22") (pintype "passive+no_connect"))
    )
    (net (code "160") (name "unconnected-(U12B-IO_L61P_1-PadU21)") (class "Default")
      (node (ref "U12") (pin "U21") (pinfunction "IO_L61P_1_U21") (pintype "passive+no_connect"))
    )
    (net (code "161") (name "unconnected-(U12B-IO_L62N_1-PadV17)") (class "Default")
      (node (ref "U12") (pin "V17") (pinfunction "IO_L62N_1_V17") (pintype "passive+no_connect"))
    )
    (net (code "162") (name "unconnected-(U12B-IO_L62P_1-PadU17)") (class "Default")
      (node (ref "U12") (pin "U17") (pinfunction "IO_L62P_1_U17") (pintype "passive+no_connect"))
    )
    (net (code "163") (name "unconnected-(U12B-IO_L63N_1-PadAA24)") (class "Default")
      (node (ref "U12") (pin "AA24") (pinfunction "IO_L63N_1_AA24") (pintype "passive+no_connect"))
    )
    (net (code "164") (name "unconnected-(U12B-IO_L63P_1-PadAA23)") (class "Default")
      (node (ref "U12") (pin "AA23") (pinfunction "IO_L63P_1_AA23") (pintype "passive+no_connect"))
    )
    (net (code "165") (name "unconnected-(U12B-IO_L64N_1-PadU20)") (class "Default")
      (node (ref "U12") (pin "U20") (pinfunction "IO_L64N_1_U20") (pintype "passive+no_connect"))
    )
    (net (code "166") (name "unconnected-(U12B-IO_L64P_1-PadT20)") (class "Default")
      (node (ref "U12") (pin "T20") (pinfunction "IO_L64P_1_T20") (pintype "passive+no_connect"))
    )
    (net (code "167") (name "unconnected-(U12B-IO_L65N_1-PadAC24)") (class "Default")
      (node (ref "U12") (pin "AC24") (pinfunction "IO_L65N_1_AC24") (pintype "passive+no_connect"))
    )
    (net (code "168") (name "unconnected-(U12B-IO_L65P_1-PadAC23)") (class "Default")
      (node (ref "U12") (pin "AC23") (pinfunction "IO_L65P_1_AC23") (pintype "passive+no_connect"))
    )
    (net (code "169") (name "unconnected-(U12B-IO_L66N_1-PadV19)") (class "Default")
      (node (ref "U12") (pin "V19") (pinfunction "IO_L66N_1_V19") (pintype "passive+no_connect"))
    )
    (net (code "170") (name "unconnected-(U12B-IO_L66P_1-PadV18)") (class "Default")
      (node (ref "U12") (pin "V18") (pinfunction "IO_L66P_1_V18") (pintype "passive+no_connect"))
    )
    (net (code "171") (name "unconnected-(U12B-IO_L67N_1-PadAF25)") (class "Default")
      (node (ref "U12") (pin "AF25") (pinfunction "IO_L67N_1_AF25") (pintype "passive+no_connect"))
    )
    (net (code "172") (name "unconnected-(U12B-IO_L67P_1-PadAE24)") (class "Default")
      (node (ref "U12") (pin "AE24") (pinfunction "IO_L67P_1_AE24") (pintype "passive+no_connect"))
    )
    (net (code "173") (name "unconnected-(U12B-IO_L68N_1-PadW19)") (class "Default")
      (node (ref "U12") (pin "W19") (pinfunction "IO_L68N_1_W19") (pintype "passive+no_connect"))
    )
    (net (code "174") (name "unconnected-(U12B-IO_L68P_1-PadW18)") (class "Default")
      (node (ref "U12") (pin "W18") (pinfunction "IO_L68P_1_W18") (pintype "passive+no_connect"))
    )
    (net (code "175") (name "unconnected-(U12B-IO_L69P_1-PadAB21)") (class "Default")
      (node (ref "U12") (pin "AB21") (pinfunction "IO_L69P_1_AB21") (pintype "passive+no_connect"))
    )
    (net (code "176") (name "unconnected-(U12B-IO_L70N_1-PadV20)") (class "Default")
      (node (ref "U12") (pin "V20") (pinfunction "IO_L70N_1_V20") (pintype "passive+no_connect"))
    )
    (net (code "177") (name "unconnected-(U12B-IO_L70P_1-PadU19)") (class "Default")
      (node (ref "U12") (pin "U19") (pinfunction "IO_L70P_1_U19") (pintype "passive+no_connect"))
    )
    (net (code "178") (name "unconnected-(U12B-IO_L71N_1-PadW22)") (class "Default")
      (node (ref "U12") (pin "W22") (pinfunction "IO_L71N_1_W22") (pintype "passive+no_connect"))
    )
    (net (code "179") (name "unconnected-(U12B-IO_L71P_1-PadV22)") (class "Default")
      (node (ref "U12") (pin "V22") (pinfunction "IO_L71P_1_V22") (pintype "passive+no_connect"))
    )
    (net (code "180") (name "unconnected-(U12B-IO_L72N_1-PadY21)") (class "Default")
      (node (ref "U12") (pin "Y21") (pinfunction "IO_L72N_1_Y21") (pintype "passive+no_connect"))
    )
    (net (code "181") (name "unconnected-(U12B-IO_L72P_1-PadY20)") (class "Default")
      (node (ref "U12") (pin "Y20") (pinfunction "IO_L72P_1_Y20") (pintype "passive+no_connect"))
    )
    (net (code "182") (name "unconnected-(U12B-IO_L73N_1-PadAA22)") (class "Default")
      (node (ref "U12") (pin "AA22") (pinfunction "IO_L73N_1_AA22") (pintype "passive+no_connect"))
    )
    (net (code "183") (name "unconnected-(U12B-IO_L73P_1-PadY22)") (class "Default")
      (node (ref "U12") (pin "Y22") (pinfunction "IO_L73P_1_Y22") (pintype "passive+no_connect"))
    )
    (net (code "184") (name "unconnected-(U12B-IO_L74N_DOUT_BUSY_1-PadAF24)") (class "Default")
      (node (ref "U12") (pin "AF24") (pinfunction "IO_L74N_DOUT_BUSY_1_AF24") (pintype "passive+no_connect"))
    )
    (net (code "185") (name "unconnected-(U12B-IO_L74P_AWAKE_1-PadAE23)") (class "Default")
      (node (ref "U12") (pin "AE23") (pinfunction "IO_L74P_AWAKE_1_AE23") (pintype "passive+no_connect"))
    )
  )
)
